# SC8701_EVM_RE1_0624.net
KiCad netlist of a schematic drawn in Altium Designer
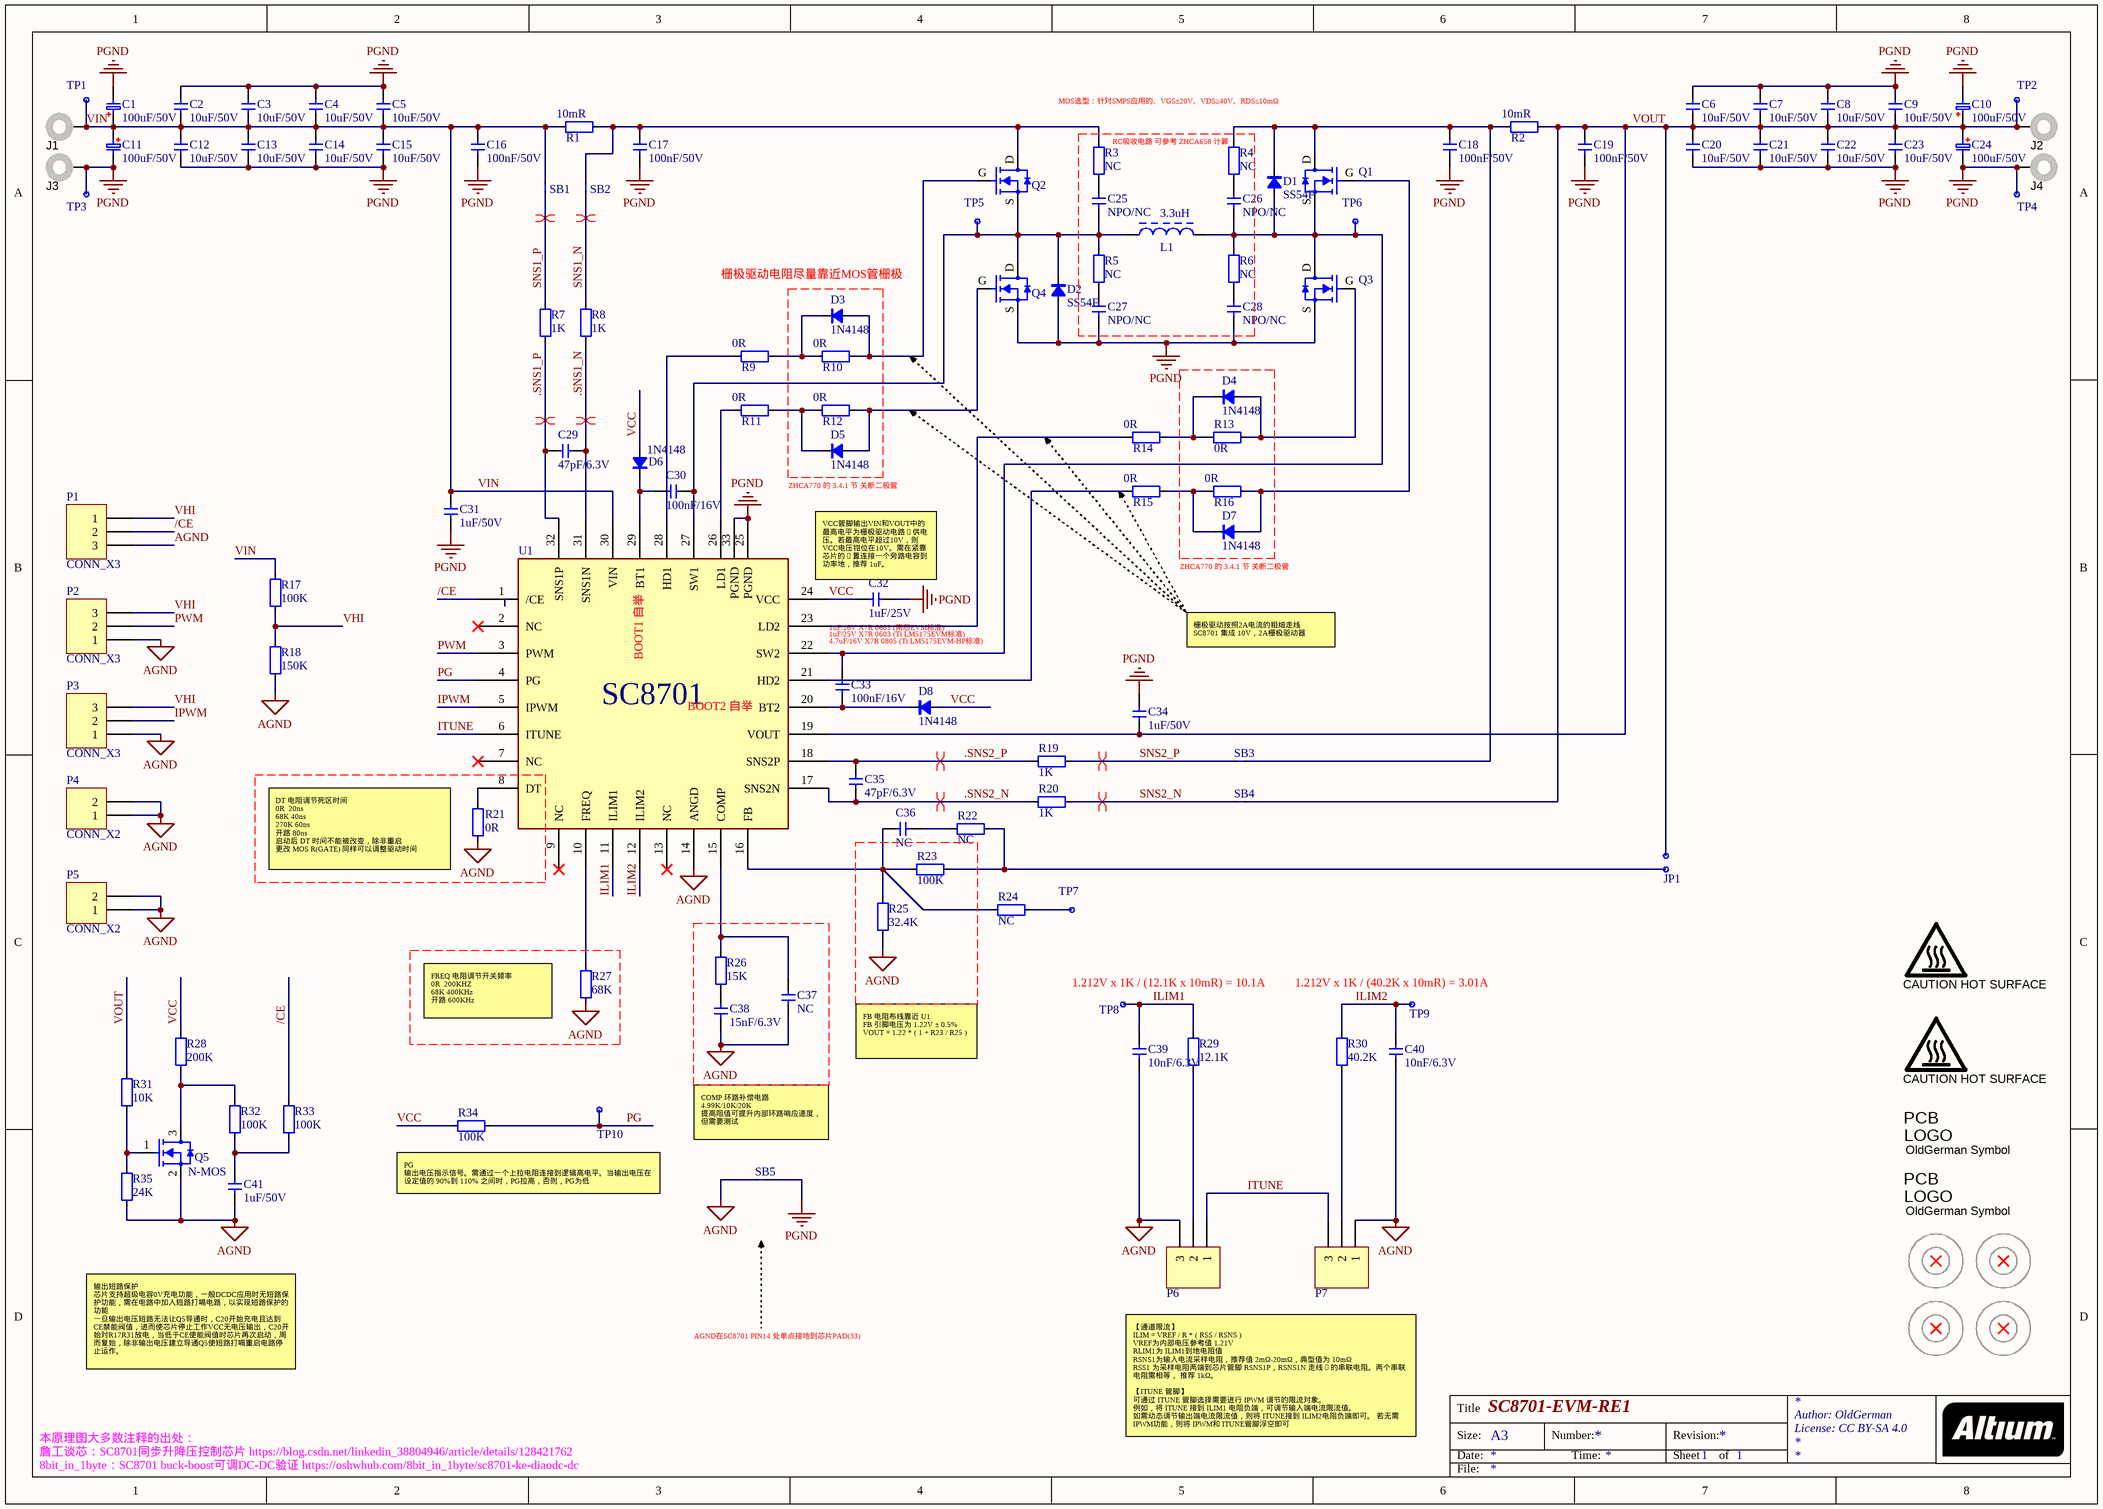
[diagram p0: SC8701_EVM_RE1_0624.SchDoc]

(export (version "E")
  (design (tool "Eeschema 10.0.6"))
  (components
    (comp (ref "C1")
      (value "100uF/50V")
      (footprint "CAP OS-CON D=10.0 L=10.0 F10")
      (description "Capacitor")
      (libsource (lib "ODG_AD_Lib") (part "CAP_Polar_Aluminum"))
    )
    (comp (ref "C2")
      (value "10uF/50V")
      (footprint "C1210")
      (description "Capacitor")
      (libsource (lib "ODG_AD_Lib") (part "CAP"))
    )
    (comp (ref "C3")
      (value "10uF/50V")
      (footprint "C1210")
      (description "Capacitor")
      (libsource (lib "ODG_AD_Lib") (part "CAP"))
    )
    (comp (ref "C4")
      (value "10uF/50V")
      (footprint "C1210")
      (description "Capacitor")
      (libsource (lib "ODG_AD_Lib") (part "CAP"))
    )
    (comp (ref "C5")
      (value "10uF/50V")
      (footprint "C1210")
      (description "Capacitor")
      (libsource (lib "ODG_AD_Lib") (part "CAP"))
    )
    (comp (ref "C6")
      (value "10uF/50V")
      (footprint "C1210")
      (description "Capacitor")
      (libsource (lib "ODG_AD_Lib") (part "CAP"))
    )
    (comp (ref "C7")
      (value "10uF/50V")
      (footprint "C1210")
      (description "Capacitor")
      (libsource (lib "ODG_AD_Lib") (part "CAP"))
    )
    (comp (ref "C8")
      (value "10uF/50V")
      (footprint "C1210")
      (description "Capacitor")
      (libsource (lib "ODG_AD_Lib") (part "CAP"))
    )
    (comp (ref "C9")
      (value "10uF/50V")
      (footprint "C1210")
      (description "Capacitor")
      (libsource (lib "ODG_AD_Lib") (part "CAP"))
    )
    (comp (ref "C10")
      (value "100uF/50V")
      (footprint "CAP OS-CON D=10.0 L=10.0 F10")
      (description "Capacitor")
      (libsource (lib "ODG_AD_Lib") (part "CAP_Polar_Aluminum"))
    )
    (comp (ref "C11")
      (value "100uF/50V")
      (footprint "CAP OS-CON D=10.0 L=10.0 F10")
      (description "Capacitor")
      (libsource (lib "ODG_AD_Lib") (part "CAP_Polar_Aluminum"))
    )
    (comp (ref "C12")
      (value "10uF/50V")
      (footprint "C1210")
      (description "Capacitor")
      (libsource (lib "ODG_AD_Lib") (part "CAP"))
    )
    (comp (ref "C13")
      (value "10uF/50V")
      (footprint "C1210")
      (description "Capacitor")
      (libsource (lib "ODG_AD_Lib") (part "CAP"))
    )
    (comp (ref "C14")
      (value "10uF/50V")
      (footprint "C1210")
      (description "Capacitor")
      (libsource (lib "ODG_AD_Lib") (part "CAP"))
    )
    (comp (ref "C15")
      (value "10uF/50V")
      (footprint "C1210")
      (description "Capacitor")
      (libsource (lib "ODG_AD_Lib") (part "CAP"))
    )
    (comp (ref "C16")
      (value "100nF/50V")
      (footprint "C0603")
      (description "Capacitor")
      (libsource (lib "ODG_AD_Lib") (part "CAP"))
    )
    (comp (ref "C17")
      (value "100nF/50V")
      (footprint "C0603")
      (description "Capacitor")
      (libsource (lib "ODG_AD_Lib") (part "CAP"))
    )
    (comp (ref "C18")
      (value "100nF/50V")
      (footprint "C0603")
      (description "Capacitor")
      (libsource (lib "ODG_AD_Lib") (part "CAP"))
    )
    (comp (ref "C19")
      (value "100nF/50V")
      (footprint "C0603")
      (description "Capacitor")
      (libsource (lib "ODG_AD_Lib") (part "CAP"))
    )
    (comp (ref "C20")
      (value "10uF/50V")
      (footprint "C1210")
      (description "Capacitor")
      (libsource (lib "ODG_AD_Lib") (part "CAP"))
    )
    (comp (ref "C21")
      (value "10uF/50V")
      (footprint "C1210")
      (description "Capacitor")
      (libsource (lib "ODG_AD_Lib") (part "CAP"))
    )
    (comp (ref "C22")
      (value "10uF/50V")
      (footprint "C1210")
      (description "Capacitor")
      (libsource (lib "ODG_AD_Lib") (part "CAP"))
    )
    (comp (ref "C23")
      (value "10uF/50V")
      (footprint "C1210")
      (description "Capacitor")
      (libsource (lib "ODG_AD_Lib") (part "CAP"))
    )
    (comp (ref "C24")
      (value "100uF/50V")
      (footprint "CAP OS-CON D=10.0 L=10.0 F10")
      (description "Capacitor")
      (libsource (lib "ODG_AD_Lib") (part "CAP_Polar_Aluminum"))
    )
    (comp (ref "C25")
      (value "NPO/NC")
      (footprint "C0805")
      (description "Capacitor")
      (libsource (lib "ODG_AD_Lib") (part "CAP"))
    )
    (comp (ref "C26")
      (value "NPO/NC")
      (footprint "C0805")
      (description "Capacitor")
      (libsource (lib "ODG_AD_Lib") (part "CAP"))
    )
    (comp (ref "C27")
      (value "NPO/NC")
      (footprint "C0805")
      (description "Capacitor")
      (libsource (lib "ODG_AD_Lib") (part "CAP"))
    )
    (comp (ref "C28")
      (value "NPO/NC")
      (footprint "C0805")
      (description "Capacitor")
      (libsource (lib "ODG_AD_Lib") (part "CAP"))
    )
    (comp (ref "C29")
      (value "47pF/6.3V")
      (footprint "C0603")
      (description "Capacitor")
      (libsource (lib "ODG_AD_Lib") (part "CAP"))
    )
    (comp (ref "C30")
      (value "100nF/16V")
      (footprint "C0603")
      (description "Capacitor")
      (libsource (lib "ODG_AD_Lib") (part "CAP"))
    )
    (comp (ref "C31")
      (value "1uF/50V")
      (footprint "C0603")
      (description "Capacitor")
      (libsource (lib "ODG_AD_Lib") (part "CAP"))
    )
    (comp (ref "C32")
      (value "1uF/25V")
      (footprint "C0805")
      (description "Capacitor")
      (libsource (lib "ODG_AD_Lib") (part "CAP"))
    )
    (comp (ref "C33")
      (value "100nF/16V")
      (footprint "C0603")
      (description "Capacitor")
      (libsource (lib "ODG_AD_Lib") (part "CAP"))
    )
    (comp (ref "C34")
      (value "1uF/50V")
      (footprint "C0603")
      (description "Capacitor")
      (libsource (lib "ODG_AD_Lib") (part "CAP"))
    )
    (comp (ref "C35")
      (value "47pF/6.3V")
      (footprint "C0603")
      (description "Capacitor")
      (libsource (lib "ODG_AD_Lib") (part "CAP"))
    )
    (comp (ref "C36")
      (value "NC")
      (footprint "C0603")
      (description "Capacitor")
      (libsource (lib "ODG_AD_Lib") (part "CAP"))
    )
    (comp (ref "C37")
      (value "NC")
      (footprint "C0603")
      (description "Capacitor")
      (libsource (lib "ODG_AD_Lib") (part "CAP"))
    )
    (comp (ref "C38")
      (value "15nF/6.3V")
      (footprint "C0603")
      (description "Capacitor")
      (libsource (lib "ODG_AD_Lib") (part "CAP"))
    )
    (comp (ref "C39")
      (value "10nF/6.3V")
      (footprint "C0603")
      (description "Capacitor")
      (libsource (lib "ODG_AD_Lib") (part "CAP"))
    )
    (comp (ref "C40")
      (value "10nF/6.3V")
      (footprint "C0603")
      (description "Capacitor")
      (libsource (lib "ODG_AD_Lib") (part "CAP"))
    )
    (comp (ref "C41")
      (value "1uF/50V")
      (footprint "C0603")
      (description "Capacitor")
      (libsource (lib "ODG_AD_Lib") (part "CAP"))
    )
    (comp (ref "D1")
      (value "SS54F")
      (footprint "SMAF")
      (description "二极管")
      (libsource (lib "") (part "DIODE_2"))
    )
    (comp (ref "D2")
      (value "SS54F")
      (footprint "SMAF")
      (description "二极管")
      (libsource (lib "") (part "DIODE_2"))
    )
    (comp (ref "D3")
      (value "1N4148")
      (footprint "SOD-323")
      (description "二极管")
      (libsource (lib "ODG_AD_Lib") (part "DIODE"))
    )
    (comp (ref "D4")
      (value "1N4148")
      (footprint "SOD-323")
      (description "二极管")
      (libsource (lib "ODG_AD_Lib") (part "DIODE"))
    )
    (comp (ref "D5")
      (value "1N4148")
      (footprint "SOD-323")
      (description "二极管")
      (libsource (lib "ODG_AD_Lib") (part "DIODE"))
    )
    (comp (ref "D6")
      (value "1N4148")
      (footprint "SOD-323")
      (description "二极管")
      (libsource (lib "") (part "DIODE_1"))
    )
    (comp (ref "D7")
      (value "1N4148")
      (footprint "SOD-323")
      (description "二极管")
      (libsource (lib "ODG_AD_Lib") (part "DIODE"))
    )
    (comp (ref "D8")
      (value "1N4148")
      (footprint "SOD-323")
      (description "二极管")
      (libsource (lib "ODG_AD_Lib") (part "DIODE"))
    )
    (comp (ref "H1") (value "HOLE") (footprint "M3.2 D=8") (libsource (lib "ODG_AD_Lib") (part "HOLE")))
    (comp (ref "H2") (value "HOLE") (footprint "M3.2 D=8") (libsource (lib "ODG_AD_Lib") (part "HOLE")))
    (comp (ref "H3") (value "HOLE") (footprint "M3.2 D=8") (libsource (lib "ODG_AD_Lib") (part "HOLE")))
    (comp (ref "H4") (value "HOLE") (footprint "M3.2 D=8") (libsource (lib "ODG_AD_Lib") (part "HOLE")))
    (comp (ref "J1")
      (value "U6047")
      (footprint "JACK_BANANA_U6047")
      (description "Banana Jack")
      (fields
        (field (name "PARTNUMBER") "575-8")
        (field (name "MANUFACTURER") "Keystone")
        (field (name "PUBLISHER") "Texas Instruments")
      )
      (libsource (lib "ODG_AD_Lib") (part "JACK_BANANA"))
    )
    (comp (ref "J2")
      (value "U6047")
      (footprint "JACK_BANANA_U6047")
      (description "Banana Jack")
      (fields
        (field (name "PARTNUMBER") "575-8")
        (field (name "MANUFACTURER") "Keystone")
        (field (name "PUBLISHER") "Texas Instruments")
      )
      (libsource (lib "ODG_AD_Lib") (part "JACK_BANANA"))
    )
    (comp (ref "J3")
      (value "U6047")
      (footprint "JACK_BANANA_U6047")
      (description "Banana Jack")
      (fields
        (field (name "PARTNUMBER") "575-8")
        (field (name "MANUFACTURER") "Keystone")
        (field (name "PUBLISHER") "Texas Instruments")
      )
      (libsource (lib "ODG_AD_Lib") (part "JACK_BANANA"))
    )
    (comp (ref "J4")
      (value "U6047")
      (footprint "JACK_BANANA_U6047")
      (description "Banana Jack")
      (fields
        (field (name "PARTNUMBER") "575-8")
        (field (name "MANUFACTURER") "Keystone")
        (field (name "PUBLISHER") "Texas Instruments")
      )
      (libsource (lib "ODG_AD_Lib") (part "JACK_BANANA"))
    )
    (comp (ref "JP1")
      (value "CONN_X2_DOT")
      (footprint "2.54mm_Male_x2")
      (libsource (lib "ODG_AD_Lib") (part "CONN_X2_DOT"))
    )
    (comp (ref "L1")
      (value "3.3uH")
      (footprint "INDUCTOR 1350 12.6X13.5X5.0mm")
      (description "135 功率电感 额定电流15A")
      (libsource (lib "ODG_AD_Lib") (part "Inductor_power"))
    )
    (comp (ref "LOGO1")
      (value "CAUTION HOT SURFACE")
      (footprint "IEC_HotSurface_Small")
      (description "IEC 61010-1 Hot Surface Warning")
      (fields (field (name "SYMBOLCREATOR") "a0412235") (field (name "PUBLISHER") "Texas Instruments"))
      (libsource (lib "ODG_AD_Lib") (part "IEC_HotSurface"))
    )
    (comp (ref "LOGO2")
      (value "CAUTION HOT SURFACE")
      (footprint "IEC_HotSurface_Small")
      (description "IEC 61010-1 Hot Surface Warning")
      (fields (field (name "SYMBOLCREATOR") "a0412235") (field (name "PUBLISHER") "Texas Instruments"))
      (libsource (lib "ODG_AD_Lib") (part "IEC_HotSurface"))
    )
    (comp (ref "Logo3")
      (value "OldGerman Symbol")
      (footprint "ODG_LOGO")
      (fields (field (name "SYMBOLCREATOR") "a0412235") (field (name "PUBLISHER") "Texas Instruments"))
      (libsource (lib "ODG_AD_Lib") (part "OldGeman"))
    )
    (comp (ref "Logo4")
      (value "OldGerman Symbol")
      (footprint "ODG_LOGO")
      (fields (field (name "SYMBOLCREATOR") "a0412235") (field (name "PUBLISHER") "Texas Instruments"))
      (libsource (lib "ODG_AD_Lib") (part "OldGeman"))
    )
    (comp (ref "P1") (value "CONN_X3") (footprint "2.54mm_Male_x3") (libsource (lib "") (part "CONN_X3_1")))
    (comp (ref "P2")
      (value "CONN_X3")
      (footprint "2.54mm_Male_x3")
      (libsource (lib "ODG_AD_Lib") (part "CONN_X3"))
    )
    (comp (ref "P3")
      (value "CONN_X3")
      (footprint "2.54mm_Male_x3")
      (libsource (lib "ODG_AD_Lib") (part "CONN_X3"))
    )
    (comp (ref "P4")
      (value "CONN_X2")
      (footprint "2.54mm_Male_x2")
      (libsource (lib "ODG_AD_Lib") (part "CONN_X2"))
    )
    (comp (ref "P5")
      (value "CONN_X2")
      (footprint "2.54mm_Male_x2")
      (libsource (lib "ODG_AD_Lib") (part "CONN_X2"))
    )
    (comp (ref "P6") (value "CONN_X3") (footprint "2.54mm_Male_x3") (libsource (lib "") (part "CONN_X3_1")))
    (comp (ref "P7") (value "CONN_X3") (footprint "2.54mm_Male_x3") (libsource (lib "") (part "CONN_X3_1")))
    (comp (ref "Q1")
      (value "N-MOS_GDS")
      (footprint "SO8FL ROUND")
      (libsource (lib "ODG_AD_Lib") (part "N-MOS_GDS"))
    )
    (comp (ref "Q2")
      (value "N-MOS_GDS")
      (footprint "SO8FL ROUND")
      (libsource (lib "ODG_AD_Lib") (part "N-MOS_GDS"))
    )
    (comp (ref "Q3")
      (value "N-MOS_GDS")
      (footprint "SO8FL ROUND")
      (libsource (lib "ODG_AD_Lib") (part "N-MOS_GDS"))
    )
    (comp (ref "Q4")
      (value "N-MOS_GDS")
      (footprint "SO8FL ROUND")
      (libsource (lib "ODG_AD_Lib") (part "N-MOS_GDS"))
    )
    (comp (ref "Q5")
      (value "N-MOS")
      (footprint "INFINEON SOT-23-3")
      (libsource (lib "ODG_AD_Lib") (part "N-MOS_123"))
    )
    (comp (ref "R1")
      (value "10mR")
      (footprint "R1206")
      (description "IEC Standard")
      (libsource (lib "ODG_AD_Lib") (part "RES"))
    )
    (comp (ref "R2")
      (value "10mR")
      (footprint "R1206")
      (description "IEC Standard")
      (libsource (lib "ODG_AD_Lib") (part "RES"))
    )
    (comp (ref "R3")
      (value "NC")
      (footprint "R0805")
      (description "IEC Standard")
      (libsource (lib "") (part "RES_1"))
    )
    (comp (ref "R4")
      (value "NC")
      (footprint "R0805")
      (description "IEC Standard")
      (libsource (lib "") (part "RES_1"))
    )
    (comp (ref "R5")
      (value "NC")
      (footprint "R0805")
      (description "IEC Standard")
      (libsource (lib "") (part "RES_1"))
    )
    (comp (ref "R6")
      (value "NC")
      (footprint "R0805")
      (description "IEC Standard")
      (libsource (lib "") (part "RES_1"))
    )
    (comp (ref "R7")
      (value "1K")
      (footprint "R0603")
      (description "IEC Standard")
      (libsource (lib "") (part "RES_1"))
    )
    (comp (ref "R8")
      (value "1K")
      (footprint "R0603")
      (description "IEC Standard")
      (libsource (lib "") (part "RES_1"))
    )
    (comp (ref "R9")
      (value "0R")
      (footprint "R0603")
      (description "IEC Standard")
      (libsource (lib "ODG_AD_Lib") (part "RES"))
    )
    (comp (ref "R10")
      (value "0R")
      (footprint "R0603")
      (description "IEC Standard")
      (libsource (lib "ODG_AD_Lib") (part "RES"))
    )
    (comp (ref "R11")
      (value "0R")
      (footprint "R0603")
      (description "IEC Standard")
      (libsource (lib "ODG_AD_Lib") (part "RES"))
    )
    (comp (ref "R12")
      (value "0R")
      (footprint "R0603")
      (description "IEC Standard")
      (libsource (lib "ODG_AD_Lib") (part "RES"))
    )
    (comp (ref "R13")
      (value "0R")
      (footprint "R0603")
      (description "IEC Standard")
      (libsource (lib "ODG_AD_Lib") (part "RES"))
    )
    (comp (ref "R14")
      (value "0R")
      (footprint "R0603")
      (description "IEC Standard")
      (libsource (lib "ODG_AD_Lib") (part "RES"))
    )
    (comp (ref "R15")
      (value "0R")
      (footprint "R0603")
      (description "IEC Standard")
      (libsource (lib "ODG_AD_Lib") (part "RES"))
    )
    (comp (ref "R16")
      (value "0R")
      (footprint "R0603")
      (description "IEC Standard")
      (libsource (lib "ODG_AD_Lib") (part "RES"))
    )
    (comp (ref "R17")
      (value "100K")
      (footprint "R0603")
      (description "IEC Standard")
      (libsource (lib "") (part "RES_1"))
    )
    (comp (ref "R18")
      (value "150K")
      (footprint "R0603")
      (description "IEC Standard")
      (libsource (lib "") (part "RES_1"))
    )
    (comp (ref "R19")
      (value "1K")
      (footprint "R0603")
      (description "IEC Standard")
      (libsource (lib "") (part "RES_2"))
    )
    (comp (ref "R20")
      (value "1K")
      (footprint "R0603")
      (description "IEC Standard")
      (libsource (lib "") (part "RES_2"))
    )
    (comp (ref "R21")
      (value "0R")
      (footprint "R0603")
      (description "IEC Standard")
      (libsource (lib "") (part "RES_1"))
    )
    (comp (ref "R22")
      (value "NC")
      (footprint "R0603")
      (description "IEC Standard")
      (libsource (lib "") (part "RES_2"))
    )
    (comp (ref "R23")
      (value "100K")
      (footprint "R0603")
      (description "IEC Standard")
      (libsource (lib "ODG_AD_Lib") (part "RES"))
    )
    (comp (ref "R24")
      (value "NC")
      (footprint "R0603")
      (description "IEC Standard")
      (libsource (lib "") (part "RES_2"))
    )
    (comp (ref "R25")
      (value "32.4K")
      (footprint "R0603")
      (description "IEC Standard")
      (libsource (lib "") (part "RES_1"))
    )
    (comp (ref "R26")
      (value "15K")
      (footprint "R0603")
      (description "IEC Standard")
      (libsource (lib "") (part "RES_1"))
    )
    (comp (ref "R27")
      (value "68K")
      (footprint "R0603")
      (description "IEC Standard")
      (libsource (lib "") (part "RES_1"))
    )
    (comp (ref "R28")
      (value "200K")
      (footprint "R0603")
      (description "IEC Standard")
      (libsource (lib "") (part "RES_1"))
    )
    (comp (ref "R29")
      (value "12.1K")
      (footprint "R0603")
      (description "IEC Standard")
      (libsource (lib "") (part "RES_1"))
    )
    (comp (ref "R30")
      (value "40.2K")
      (footprint "R0603")
      (description "IEC Standard")
      (libsource (lib "") (part "RES_1"))
    )
    (comp (ref "R31")
      (value "10K")
      (footprint "R0603")
      (description "IEC Standard")
      (libsource (lib "") (part "RES_1"))
    )
    (comp (ref "R32")
      (value "100K")
      (footprint "R0603")
      (description "IEC Standard")
      (libsource (lib "") (part "RES_1"))
    )
    (comp (ref "R33")
      (value "100K")
      (footprint "R0603")
      (description "IEC Standard")
      (libsource (lib "") (part "RES_1"))
    )
    (comp (ref "R34")
      (value "100K")
      (footprint "R0603")
      (description "IEC Standard")
      (libsource (lib "ODG_AD_Lib") (part "RES"))
    )
    (comp (ref "R35")
      (value "24K")
      (footprint "R0603")
      (description "IEC Standard")
      (libsource (lib "") (part "RES_1"))
    )
    (comp (ref "SB1")
      (value "NetTie_200um")
      (footprint "NetTie_200um")
      (description "Net Tie")
      (fields (field (name "PART NUMBER") "NetTie 0.2mm") (field (name "PUBLISHER") "Nordic Semiconductor"))
      (libsource (lib "pca63100") (part "NetTie 0.2mm"))
    )
    (comp (ref "SB2")
      (value "NetTie_200um")
      (footprint "NetTie_200um")
      (description "Net Tie")
      (fields (field (name "PART NUMBER") "NetTie 0.2mm") (field (name "PUBLISHER") "Nordic Semiconductor"))
      (libsource (lib "pca63100") (part "NetTie 0.2mm"))
    )
    (comp (ref "SB3")
      (value "NetTie_200um")
      (footprint "NetTie_200um")
      (description "Net Tie")
      (fields (field (name "PART NUMBER") "NetTie 0.2mm") (field (name "PUBLISHER") "Nordic Semiconductor"))
      (libsource (lib "pca63100") (part "NetTie 0.2mm"))
    )
    (comp (ref "SB4")
      (value "NetTie_200um")
      (footprint "NetTie_200um")
      (description "Net Tie")
      (fields (field (name "PART NUMBER") "NetTie 0.2mm") (field (name "PUBLISHER") "Nordic Semiconductor"))
      (libsource (lib "pca63100") (part "NetTie 0.2mm"))
    )
    (comp (ref "SB5")
      (value "NetTie_200um")
      (footprint "NetTie_200um")
      (description "Net Tie")
      (fields (field (name "PART NUMBER") "NetTie 0.2mm") (field (name "PUBLISHER") "Nordic Semiconductor"))
      (libsource (lib "pca63100") (part "NetTie 0.2mm"))
    )
    (comp (ref "TP1")
      (value "CONN_X1_DOT")
      (footprint "2.54mm_Male_x1")
      (libsource (lib "ODG_AD_Lib") (part "CONN_X1_DOT"))
    )
    (comp (ref "TP2")
      (value "CONN_X1_DOT")
      (footprint "2.54mm_Male_x1")
      (libsource (lib "ODG_AD_Lib") (part "CONN_X1_DOT"))
    )
    (comp (ref "TP3")
      (value "CONN_X1_DOT")
      (footprint "2.54mm_Male_x1")
      (libsource (lib "ODG_AD_Lib") (part "CONN_X1_DOT"))
    )
    (comp (ref "TP4")
      (value "CONN_X1_DOT")
      (footprint "2.54mm_Male_x1")
      (libsource (lib "ODG_AD_Lib") (part "CONN_X1_DOT"))
    )
    (comp (ref "TP5")
      (value "CONN_X1_DOT")
      (footprint "2.54mm_Male_x1")
      (libsource (lib "ODG_AD_Lib") (part "CONN_X1_DOT"))
    )
    (comp (ref "TP6")
      (value "CONN_X1_DOT")
      (footprint "2.54mm_Male_x1")
      (libsource (lib "ODG_AD_Lib") (part "CONN_X1_DOT"))
    )
    (comp (ref "TP7")
      (value "CONN_X1_DOT")
      (footprint "2.54mm_Male_x1")
      (libsource (lib "ODG_AD_Lib") (part "CONN_X1_DOT"))
    )
    (comp (ref "TP8")
      (value "CONN_X1_DOT")
      (footprint "2.54mm_Male_x1")
      (libsource (lib "ODG_AD_Lib") (part "CONN_X1_DOT"))
    )
    (comp (ref "TP9")
      (value "CONN_X1_DOT")
      (footprint "2.54mm_Male_x1")
      (libsource (lib "ODG_AD_Lib") (part "CONN_X1_DOT"))
    )
    (comp (ref "TP10")
      (value "CONN_X1_DOT")
      (footprint "2.54mm_Male_x1")
      (libsource (lib "ODG_AD_Lib") (part "CONN_X1_DOT"))
    )
    (comp (ref "U1")
      (value "SC8701 (A)")
      (footprint "TQFN-32 4X4MM 0.4 VIA")
      (description "高效率, 同步, 4 管升降压控制器")
      (libsource (lib "ODG_AD_Lib") (part "SC8701 (A)"))
    )
  )
  (nets
    (net (code "1") (name "/.SNS1_N") (class "Default")
      (node (ref "C29") (pin "2") (pinfunction "2_2") (pintype "passive"))
      (node (ref "R8") (pin "1") (pinfunction "1_1") (pintype "passive"))
      (node (ref "U1") (pin "31") (pinfunction "SNS1N_31") (pintype "passive"))
    )
    (net (code "2") (name "/.SNS1_P") (class "Default")
      (node (ref "C29") (pin "1") (pinfunction "1_1") (pintype "passive"))
      (node (ref "R7") (pin "1") (pinfunction "1_1") (pintype "passive"))
      (node (ref "U1") (pin "32") (pinfunction "SNS1P_32") (pintype "passive"))
    )
    (net (code "3") (name "/.SNS2_N") (class "Default")
      (node (ref "C35") (pin "2") (pinfunction "2_2") (pintype "passive"))
      (node (ref "R20") (pin "2") (pinfunction "2_2") (pintype "passive"))
      (node (ref "U1") (pin "17") (pinfunction "SNS2N_17") (pintype "passive"))
    )
    (net (code "4") (name "/.SNS2_P") (class "Default")
      (node (ref "C35") (pin "1") (pinfunction "1_1") (pintype "passive"))
      (node (ref "R19") (pin "2") (pinfunction "2_2") (pintype "passive"))
      (node (ref "U1") (pin "18") (pinfunction "SNS2P_18") (pintype "passive"))
    )
    (net (code "5") (name "/ILIM1") (class "Default")
      (node (ref "C39") (pin "2") (pinfunction "2_2") (pintype "passive"))
      (node (ref "R29") (pin "2") (pinfunction "2_2") (pintype "passive"))
      (node (ref "TP8") (pin "1") (pinfunction "1_1") (pintype "passive"))
      (node (ref "U1") (pin "11") (pinfunction "ILIM1_11") (pintype "passive"))
    )
    (net (code "6") (name "/ILIM2") (class "Default")
      (node (ref "C40") (pin "2") (pinfunction "2_2") (pintype "passive"))
      (node (ref "R30") (pin "2") (pinfunction "2_2") (pintype "passive"))
      (node (ref "TP9") (pin "1") (pinfunction "1_1") (pintype "passive"))
      (node (ref "U1") (pin "12") (pinfunction "ILIM2_12") (pintype "passive"))
    )
    (net (code "7") (name "/IPWM") (class "Default")
      (node (ref "P3") (pin "2") (pinfunction "2_2") (pintype "passive"))
      (node (ref "U1") (pin "5") (pinfunction "IPWM_5") (pintype "passive"))
    )
    (net (code "8") (name "/ITUNE") (class "Default")
      (node (ref "P6") (pin "1") (pinfunction "1_1") (pintype "passive"))
      (node (ref "P7") (pin "3") (pinfunction "3_3") (pintype "passive"))
      (node (ref "U1") (pin "6") (pinfunction "ITUNE_6") (pintype "passive"))
    )
    (net (code "9") (name "/PG") (class "Default")
      (node (ref "R34") (pin "2") (pinfunction "2_2") (pintype "passive"))
      (node (ref "TP10") (pin "1") (pinfunction "1_1") (pintype "passive"))
      (node (ref "U1") (pin "4") (pinfunction "PG_4") (pintype "passive"))
    )
    (net (code "10") (name "/PWM") (class "Default")
      (node (ref "P2") (pin "2") (pinfunction "2_2") (pintype "passive"))
      (node (ref "U1") (pin "3") (pinfunction "PWM_3") (pintype "passive"))
    )
    (net (code "11") (name "/SNS1_N") (class "Default")
      (node (ref "R8") (pin "2") (pinfunction "2_2") (pintype "passive"))
      (node (ref "SB2") (pin "1") (pinfunction "1_1") (pintype "passive"))
    )
    (net (code "12") (name "/SNS1_P") (class "Default")
      (node (ref "R7") (pin "2") (pinfunction "2_2") (pintype "passive"))
      (node (ref "SB1") (pin "1") (pinfunction "1_1") (pintype "passive"))
    )
    (net (code "13") (name "/SNS2_N") (class "Default")
      (node (ref "R20") (pin "1") (pinfunction "1_1") (pintype "passive"))
      (node (ref "SB4") (pin "1") (pinfunction "1_1") (pintype "passive"))
    )
    (net (code "14") (name "/SNS2_P") (class "Default")
      (node (ref "R19") (pin "1") (pinfunction "1_1") (pintype "passive"))
      (node (ref "SB3") (pin "1") (pinfunction "1_1") (pintype "passive"))
    )
    (net (code "15") (name "/VCC") (class "Default")
      (node (ref "C32") (pin "1") (pinfunction "1_1") (pintype "passive"))
      (node (ref "D6") (pin "1") (pinfunction "A_1") (pintype "passive"))
      (node (ref "D8") (pin "1") (pinfunction "A_1") (pintype "passive"))
      (node (ref "R28") (pin "2") (pinfunction "2_2") (pintype "passive"))
      (node (ref "R34") (pin "1") (pinfunction "1_1") (pintype "passive"))
      (node (ref "U1") (pin "24") (pinfunction "VCC_24") (pintype "passive"))
    )
    (net (code "16") (name "/VHI") (class "Default")
      (node (ref "P1") (pin "1") (pinfunction "1_1") (pintype "passive"))
      (node (ref "P2") (pin "3") (pinfunction "3_3") (pintype "passive"))
      (node (ref "P3") (pin "3") (pinfunction "3_3") (pintype "passive"))
      (node (ref "R17") (pin "1") (pinfunction "1_1") (pintype "passive"))
      (node (ref "R18") (pin "2") (pinfunction "2_2") (pintype "passive"))
    )
    (net (code "17") (name "/VIN") (class "Default")
      (node (ref "C1") (pin "1") (pinfunction "1_1") (pintype "passive"))
      (node (ref "C11") (pin "1") (pinfunction "1_1") (pintype "passive"))
      (node (ref "C12") (pin "2") (pinfunction "2_2") (pintype "passive"))
      (node (ref "C13") (pin "2") (pinfunction "2_2") (pintype "passive"))
      (node (ref "C14") (pin "2") (pinfunction "2_2") (pintype "passive"))
      (node (ref "C15") (pin "2") (pinfunction "2_2") (pintype "passive"))
      (node (ref "C16") (pin "2") (pinfunction "2_2") (pintype "passive"))
      (node (ref "C2") (pin "2") (pinfunction "2_2") (pintype "passive"))
      (node (ref "C3") (pin "2") (pinfunction "2_2") (pintype "passive"))
      (node (ref "C31") (pin "1") (pinfunction "1_1") (pintype "passive"))
      (node (ref "C4") (pin "2") (pinfunction "2_2") (pintype "passive"))
      (node (ref "C5") (pin "2") (pinfunction "2_2") (pintype "passive"))
      (node (ref "J1") (pin "1") (pinfunction "1_1") (pintype "passive"))
      (node (ref "R1") (pin "1") (pinfunction "1_1") (pintype "passive"))
      (node (ref "R17") (pin "2") (pinfunction "2_2") (pintype "passive"))
      (node (ref "SB1") (pin "2") (pinfunction "2_2") (pintype "passive"))
      (node (ref "TP1") (pin "1") (pinfunction "1_1") (pintype "passive"))
      (node (ref "U1") (pin "30") (pinfunction "VIN_30") (pintype "passive"))
    )
    (net (code "18") (name "/VOUT") (class "Default")
      (node (ref "C10") (pin "1") (pinfunction "1_1") (pintype "passive"))
      (node (ref "C19") (pin "2") (pinfunction "2_2") (pintype "passive"))
      (node (ref "C20") (pin "2") (pinfunction "2_2") (pintype "passive"))
      (node (ref "C21") (pin "2") (pinfunction "2_2") (pintype "passive"))
      (node (ref "C22") (pin "2") (pinfunction "2_2") (pintype "passive"))
      (node (ref "C23") (pin "2") (pinfunction "2_2") (pintype "passive"))
      (node (ref "C24") (pin "1") (pinfunction "1_1") (pintype "passive"))
      (node (ref "C34") (pin "1") (pinfunction "1_1") (pintype "passive"))
      (node (ref "C6") (pin "2") (pinfunction "2_2") (pintype "passive"))
      (node (ref "C7") (pin "2") (pinfunction "2_2") (pintype "passive"))
      (node (ref "C8") (pin "2") (pinfunction "2_2") (pintype "passive"))
      (node (ref "C9") (pin "2") (pinfunction "2_2") (pintype "passive"))
      (node (ref "J2") (pin "1") (pinfunction "1_1") (pintype "passive"))
      (node (ref "JP1") (pin "1") (pinfunction "1_1") (pintype "passive"))
      (node (ref "R2") (pin "2") (pinfunction "2_2") (pintype "passive"))
      (node (ref "R31") (pin "2") (pinfunction "2_2") (pintype "passive"))
      (node (ref "SB4") (pin "2") (pinfunction "2_2") (pintype "passive"))
      (node (ref "TP2") (pin "1") (pinfunction "1_1") (pintype "passive"))
      (node (ref "U1") (pin "19") (pinfunction "VOUT_19") (pintype "passive"))
    )
    (net (code "19") (name "/{slash}CE") (class "Default")
      (node (ref "P1") (pin "2") (pinfunction "2_2") (pintype "passive"))
      (node (ref "R33") (pin "2") (pinfunction "2_2") (pintype "passive"))
      (node (ref "U1") (pin "1") (pinfunction "/CE_1") (pintype "passive"))
    )
    (net (code "20") (name "AGND") (class "Default")
      (node (ref "C37") (pin "1") (pinfunction "1_1") (pintype "passive"))
      (node (ref "C38") (pin "1") (pinfunction "1_1") (pintype "passive"))
      (node (ref "C39") (pin "1") (pinfunction "1_1") (pintype "passive"))
      (node (ref "C40") (pin "1") (pinfunction "1_1") (pintype "passive"))
      (node (ref "C41") (pin "2") (pinfunction "2_2") (pintype "passive"))
      (node (ref "P1") (pin "3") (pinfunction "3_3") (pintype "passive"))
      (node (ref "P2") (pin "1") (pinfunction "1_1") (pintype "passive"))
      (node (ref "P3") (pin "1") (pinfunction "1_1") (pintype "passive"))
      (node (ref "P4") (pin "1") (pinfunction "1_1") (pintype "passive"))
      (node (ref "P4") (pin "2") (pinfunction "2_2") (pintype "passive"))
      (node (ref "P5") (pin "1") (pinfunction "1_1") (pintype "passive"))
      (node (ref "P5") (pin "2") (pinfunction "2_2") (pintype "passive"))
      (node (ref "P6") (pin "3") (pinfunction "3_3") (pintype "passive"))
      (node (ref "P7") (pin "1") (pinfunction "1_1") (pintype "passive"))
      (node (ref "Q5") (pin "2") (pinfunction "S_2") (pintype "passive"))
      (node (ref "R18") (pin "1") (pinfunction "1_1") (pintype "passive"))
      (node (ref "R21") (pin "1") (pinfunction "1_1") (pintype "passive"))
      (node (ref "R25") (pin "1") (pinfunction "1_1") (pintype "passive"))
      (node (ref "R27") (pin "1") (pinfunction "1_1") (pintype "passive"))
      (node (ref "R35") (pin "1") (pinfunction "1_1") (pintype "passive"))
      (node (ref "SB5") (pin "1") (pinfunction "1_1") (pintype "passive"))
      (node (ref "U1") (pin "14") (pinfunction "ANGD_14") (pintype "passive"))
    )
    (net (code "21") (name "Net-(C17-Pad2)") (class "Default")
      (node (ref "C17") (pin "2") (pinfunction "2_2") (pintype "passive"))
      (node (ref "Q2") (pin "D") (pinfunction "D_D") (pintype "passive"))
      (node (ref "R1") (pin "2") (pinfunction "2_2") (pintype "passive"))
      (node (ref "R3") (pin "2") (pinfunction "2_2") (pintype "passive"))
      (node (ref "SB2") (pin "2") (pinfunction "2_2") (pintype "passive"))
    )
    (net (code "22") (name "Net-(C25-Pad2)") (class "Default")
      (node (ref "C25") (pin "2") (pinfunction "2_2") (pintype "passive"))
      (node (ref "R3") (pin "1") (pinfunction "1_1") (pintype "passive"))
    )
    (net (code "23") (name "Net-(C26-Pad2)") (class "Default")
      (node (ref "C26") (pin "2") (pinfunction "2_2") (pintype "passive"))
      (node (ref "R4") (pin "1") (pinfunction "1_1") (pintype "passive"))
    )
    (net (code "24") (name "Net-(C27-Pad2)") (class "Default")
      (node (ref "C27") (pin "2") (pinfunction "2_2") (pintype "passive"))
      (node (ref "R5") (pin "1") (pinfunction "1_1") (pintype "passive"))
    )
    (net (code "25") (name "Net-(C28-Pad2)") (class "Default")
      (node (ref "C28") (pin "2") (pinfunction "2_2") (pintype "passive"))
      (node (ref "R6") (pin "1") (pinfunction "1_1") (pintype "passive"))
    )
    (net (code "26") (name "Net-(C36-Pad2)") (class "Default")
      (node (ref "C36") (pin "2") (pinfunction "2_2") (pintype "passive"))
      (node (ref "R22") (pin "2") (pinfunction "2_2") (pintype "passive"))
    )
    (net (code "27") (name "Net-(C38-Pad2)") (class "Default")
      (node (ref "C38") (pin "2") (pinfunction "2_2") (pintype "passive"))
      (node (ref "R26") (pin "1") (pinfunction "1_1") (pintype "passive"))
    )
    (net (code "28") (name "Net-(C41-Pad1)") (class "Default")
      (node (ref "C41") (pin "1") (pinfunction "1_1") (pintype "passive"))
      (node (ref "R32") (pin "1") (pinfunction "1_1") (pintype "passive"))
      (node (ref "R33") (pin "1") (pinfunction "1_1") (pintype "passive"))
    )
    (net (code "29") (name "Net-(D1-A)") (class "Default")
      (node (ref "C26") (pin "1") (pinfunction "1_1") (pintype "passive"))
      (node (ref "C33") (pin "1") (pinfunction "1_1") (pintype "passive"))
      (node (ref "D1") (pin "1") (pinfunction "A_1") (pintype "passive"))
      (node (ref "L1") (pin "2") (pinfunction "2_2") (pintype "passive"))
      (node (ref "Q1") (pin "S") (pinfunction "S_S") (pintype "passive"))
      (node (ref "Q3") (pin "D") (pinfunction "D_D") (pintype "passive"))
      (node (ref "R6") (pin "2") (pinfunction "2_2") (pintype "passive"))
      (node (ref "TP6") (pin "1") (pinfunction "1_1") (pintype "passive"))
      (node (ref "U1") (pin "22") (pinfunction "SW2_22") (pintype "passive"))
    )
    (net (code "30") (name "Net-(D1-C)") (class "Default")
      (node (ref "C18") (pin "2") (pinfunction "2_2") (pintype "passive"))
      (node (ref "D1") (pin "2") (pinfunction "C_2") (pintype "passive"))
      (node (ref "Q1") (pin "D") (pinfunction "D_D") (pintype "passive"))
      (node (ref "R2") (pin "1") (pinfunction "1_1") (pintype "passive"))
      (node (ref "R4") (pin "2") (pinfunction "2_2") (pintype "passive"))
      (node (ref "SB3") (pin "2") (pinfunction "2_2") (pintype "passive"))
    )
    (net (code "31") (name "Net-(D2-C)") (class "Default")
      (node (ref "C25") (pin "1") (pinfunction "1_1") (pintype "passive"))
      (node (ref "C30") (pin "2") (pinfunction "2_2") (pintype "passive"))
      (node (ref "D2") (pin "2") (pinfunction "C_2") (pintype "passive"))
      (node (ref "L1") (pin "1") (pintype "passive"))
      (node (ref "Q2") (pin "S") (pinfunction "S_S") (pintype "passive"))
      (node (ref "Q4") (pin "D") (pinfunction "D_D") (pintype "passive"))
      (node (ref "R5") (pin "2") (pinfunction "2_2") (pintype "passive"))
      (node (ref "TP5") (pin "1") (pinfunction "1_1") (pintype "passive"))
      (node (ref "U1") (pin "27") (pinfunction "SW1_27") (pintype "passive"))
    )
    (net (code "32") (name "Net-(D3-A)") (class "Default")
      (node (ref "D3") (pin "1") (pinfunction "A_1") (pintype "passive"))
      (node (ref "Q2") (pin "G") (pinfunction "G_G") (pintype "passive"))
      (node (ref "R10") (pin "2") (pinfunction "2_2") (pintype "passive"))
    )
    (net (code "33") (name "Net-(D3-C)") (class "Default")
      (node (ref "D3") (pin "2") (pinfunction "C_2") (pintype "passive"))
      (node (ref "R10") (pin "1") (pinfunction "1_1") (pintype "passive"))
      (node (ref "R9") (pin "2") (pinfunction "2_2") (pintype "passive"))
    )
    (net (code "34") (name "Net-(D4-A)") (class "Default")
      (node (ref "D4") (pin "1") (pinfunction "A_1") (pintype "passive"))
      (node (ref "Q3") (pin "G") (pinfunction "G_G") (pintype "passive"))
      (node (ref "R13") (pin "2") (pinfunction "2_2") (pintype "passive"))
    )
    (net (code "35") (name "Net-(D4-C)") (class "Default")
      (node (ref "D4") (pin "2") (pinfunction "C_2") (pintype "passive"))
      (node (ref "R13") (pin "1") (pinfunction "1_1") (pintype "passive"))
      (node (ref "R14") (pin "2") (pinfunction "2_2") (pintype "passive"))
    )
    (net (code "36") (name "Net-(D5-A)") (class "Default")
      (node (ref "D5") (pin "1") (pinfunction "A_1") (pintype "passive"))
      (node (ref "Q4") (pin "G") (pinfunction "G_G") (pintype "passive"))
      (node (ref "R12") (pin "2") (pinfunction "2_2") (pintype "passive"))
    )
    (net (code "37") (name "Net-(D5-C)") (class "Default")
      (node (ref "D5") (pin "2") (pinfunction "C_2") (pintype "passive"))
      (node (ref "R11") (pin "2") (pinfunction "2_2") (pintype "passive"))
      (node (ref "R12") (pin "1") (pinfunction "1_1") (pintype "passive"))
    )
    (net (code "38") (name "Net-(D6-C)") (class "Default")
      (node (ref "C30") (pin "1") (pinfunction "1_1") (pintype "passive"))
      (node (ref "D6") (pin "2") (pinfunction "C_2") (pintype "passive"))
      (node (ref "U1") (pin "29") (pinfunction "BT1_29") (pintype "passive"))
    )
    (net (code "39") (name "Net-(D7-A)") (class "Default")
      (node (ref "D7") (pin "1") (pinfunction "A_1") (pintype "passive"))
      (node (ref "Q1") (pin "G") (pinfunction "G_G") (pintype "passive"))
      (node (ref "R16") (pin "2") (pinfunction "2_2") (pintype "passive"))
    )
    (net (code "40") (name "Net-(D7-C)") (class "Default")
      (node (ref "D7") (pin "2") (pinfunction "C_2") (pintype "passive"))
      (node (ref "R15") (pin "2") (pinfunction "2_2") (pintype "passive"))
      (node (ref "R16") (pin "1") (pinfunction "1_1") (pintype "passive"))
    )
    (net (code "41") (name "Net-(D8-C)") (class "Default")
      (node (ref "C33") (pin "2") (pinfunction "2_2") (pintype "passive"))
      (node (ref "D8") (pin "2") (pinfunction "C_2") (pintype "passive"))
      (node (ref "U1") (pin "20") (pinfunction "BT2_20") (pintype "passive"))
    )
    (net (code "42") (name "Net-(JP1-Pad2)") (class "Default")
      (node (ref "JP1") (pin "2") (pinfunction "2_2") (pintype "passive"))
      (node (ref "R22") (pin "1") (pinfunction "1_1") (pintype "passive"))
      (node (ref "R23") (pin "2") (pinfunction "2_2") (pintype "passive"))
    )
    (net (code "43") (name "Net-(P6-Pad2)") (class "Default")
      (node (ref "P6") (pin "2") (pinfunction "2_2") (pintype "passive"))
      (node (ref "R29") (pin "1") (pinfunction "1_1") (pintype "passive"))
    )
    (net (code "44") (name "Net-(P7-Pad2)") (class "Default")
      (node (ref "P7") (pin "2") (pinfunction "2_2") (pintype "passive"))
      (node (ref "R30") (pin "1") (pinfunction "1_1") (pintype "passive"))
    )
    (net (code "45") (name "Net-(Q5-D)") (class "Default")
      (node (ref "Q5") (pin "3") (pinfunction "D_3") (pintype "passive"))
      (node (ref "R28") (pin "1") (pinfunction "1_1") (pintype "passive"))
      (node (ref "R32") (pin "2") (pinfunction "2_2") (pintype "passive"))
    )
    (net (code "46") (name "Net-(Q5-G)") (class "Default")
      (node (ref "Q5") (pin "1") (pinfunction "G_1") (pintype "passive"))
      (node (ref "R31") (pin "1") (pinfunction "1_1") (pintype "passive"))
      (node (ref "R35") (pin "2") (pinfunction "2_2") (pintype "passive"))
    )
    (net (code "47") (name "Net-(R24-Pad1)") (class "Default")
      (node (ref "R24") (pin "1") (pinfunction "1_1") (pintype "passive"))
      (node (ref "TP7") (pin "1") (pinfunction "1_1") (pintype "passive"))
    )
    (net (code "48") (name "Net-(U1-COMP)") (class "Default")
      (node (ref "C37") (pin "2") (pinfunction "2_2") (pintype "passive"))
      (node (ref "R26") (pin "2") (pinfunction "2_2") (pintype "passive"))
      (node (ref "U1") (pin "15") (pinfunction "COMP_15") (pintype "passive"))
    )
    (net (code "49") (name "Net-(U1-DT)") (class "Default")
      (node (ref "R21") (pin "2") (pinfunction "2_2") (pintype "passive"))
      (node (ref "U1") (pin "8") (pinfunction "DT_8") (pintype "passive"))
    )
    (net (code "50") (name "Net-(U1-FB)") (class "Default")
      (node (ref "C36") (pin "1") (pinfunction "1_1") (pintype "passive"))
      (node (ref "R23") (pin "1") (pinfunction "1_1") (pintype "passive"))
      (node (ref "R24") (pin "2") (pinfunction "2_2") (pintype "passive"))
      (node (ref "R25") (pin "2") (pinfunction "2_2") (pintype "passive"))
      (node (ref "U1") (pin "16") (pinfunction "FB_16") (pintype "passive"))
    )
    (net (code "51") (name "Net-(U1-FREQ)") (class "Default")
      (node (ref "R27") (pin "2") (pinfunction "2_2") (pintype "passive"))
      (node (ref "U1") (pin "10") (pinfunction "FREQ_10") (pintype "passive"))
    )
    (net (code "52") (name "Net-(U1-HD1)") (class "Default")
      (node (ref "R9") (pin "1") (pinfunction "1_1") (pintype "passive"))
      (node (ref "U1") (pin "28") (pinfunction "HD1_28") (pintype "passive"))
    )
    (net (code "53") (name "Net-(U1-HD2)") (class "Default")
      (node (ref "R15") (pin "1") (pinfunction "1_1") (pintype "passive"))
      (node (ref "U1") (pin "21") (pinfunction "HD2_21") (pintype "passive"))
    )
    (net (code "54") (name "Net-(U1-LD1)") (class "Default")
      (node (ref "R11") (pin "1") (pinfunction "1_1") (pintype "passive"))
      (node (ref "U1") (pin "26") (pinfunction "LD1_26") (pintype "passive"))
    )
    (net (code "55") (name "Net-(U1-LD2)") (class "Default")
      (node (ref "R14") (pin "1") (pinfunction "1_1") (pintype "passive"))
      (node (ref "U1") (pin "23") (pinfunction "LD2_23") (pintype "passive"))
    )
    (net (code "56") (name "PGND") (class "Default")
      (node (ref "C1") (pin "2") (pinfunction "2_2") (pintype "passive"))
      (node (ref "C10") (pin "2") (pinfunction "2_2") (pintype "passive"))
      (node (ref "C11") (pin "2") (pinfunction "2_2") (pintype "passive"))
      (node (ref "C12") (pin "1") (pinfunction "1_1") (pintype "passive"))
      (node (ref "C13") (pin "1") (pinfunction "1_1") (pintype "passive"))
      (node (ref "C14") (pin "1") (pinfunction "1_1") (pintype "passive"))
      (node (ref "C15") (pin "1") (pinfunction "1_1") (pintype "passive"))
      (node (ref "C16") (pin "1") (pinfunction "1_1") (pintype "passive"))
      (node (ref "C17") (pin "1") (pinfunction "1_1") (pintype "passive"))
      (node (ref "C18") (pin "1") (pinfunction "1_1") (pintype "passive"))
      (node (ref "C19") (pin "1") (pinfunction "1_1") (pintype "passive"))
      (node (ref "C2") (pin "1") (pinfunction "1_1") (pintype "passive"))
      (node (ref "C20") (pin "1") (pinfunction "1_1") (pintype "passive"))
      (node (ref "C21") (pin "1") (pinfunction "1_1") (pintype "passive"))
      (node (ref "C22") (pin "1") (pinfunction "1_1") (pintype "passive"))
      (node (ref "C23") (pin "1") (pinfunction "1_1") (pintype "passive"))
      (node (ref "C24") (pin "2") (pinfunction "2_2") (pintype "passive"))
      (node (ref "C27") (pin "1") (pinfunction "1_1") (pintype "passive"))
      (node (ref "C28") (pin "1") (pinfunction "1_1") (pintype "passive"))
      (node (ref "C3") (pin "1") (pinfunction "1_1") (pintype "passive"))
      (node (ref "C31") (pin "2") (pinfunction "2_2") (pintype "passive"))
      (node (ref "C32") (pin "2") (pinfunction "2_2") (pintype "passive"))
      (node (ref "C34") (pin "2") (pinfunction "2_2") (pintype "passive"))
      (node (ref "C4") (pin "1") (pinfunction "1_1") (pintype "passive"))
      (node (ref "C5") (pin "1") (pinfunction "1_1") (pintype "passive"))
      (node (ref "C6") (pin "1") (pinfunction "1_1") (pintype "passive"))
      (node (ref "C7") (pin "1") (pinfunction "1_1") (pintype "passive"))
      (node (ref "C8") (pin "1") (pinfunction "1_1") (pintype "passive"))
      (node (ref "C9") (pin "1") (pinfunction "1_1") (pintype "passive"))
      (node (ref "D2") (pin "1") (pinfunction "A_1") (pintype "passive"))
      (node (ref "J3") (pin "1") (pinfunction "1_1") (pintype "passive"))
      (node (ref "J4") (pin "1") (pinfunction "1_1") (pintype "passive"))
      (node (ref "Q3") (pin "S") (pinfunction "S_S") (pintype "passive"))
      (node (ref "Q4") (pin "S") (pinfunction "S_S") (pintype "passive"))
      (node (ref "SB5") (pin "2") (pinfunction "2_2") (pintype "passive"))
      (node (ref "TP3") (pin "1") (pinfunction "1_1") (pintype "passive"))
      (node (ref "TP4") (pin "1") (pinfunction "1_1") (pintype "passive"))
      (node (ref "U1") (pin "25") (pinfunction "PGND_25") (pintype "passive"))
      (node (ref "U1") (pin "33") (pinfunction "PGND_33") (pintype "passive"))
    )
    (net (code "57") (name "unconnected-(H1-Pad1)") (class "Default")
      (node (ref "H1") (pin "1") (pinfunction "1_1") (pintype "passive+no_connect"))
    )
    (net (code "58") (name "unconnected-(H2-Pad1)") (class "Default")
      (node (ref "H2") (pin "1") (pinfunction "1_1") (pintype "passive+no_connect"))
    )
    (net (code "59") (name "unconnected-(H3-Pad1)") (class "Default")
      (node (ref "H3") (pin "1") (pinfunction "1_1") (pintype "passive+no_connect"))
    )
    (net (code "60") (name "unconnected-(H4-Pad1)") (class "Default")
      (node (ref "H4") (pin "1") (pinfunction "1_1") (pintype "passive+no_connect"))
    )
    (net (code "61") (name "unconnected-(U1-NC-Pad2)") (class "Default")
      (node (ref "U1") (pin "2") (pinfunction "NC_2") (pintype "passive+no_connect"))
    )
    (net (code "62") (name "unconnected-(U1-NC-Pad7)") (class "Default")
      (node (ref "U1") (pin "7") (pinfunction "NC_7") (pintype "passive+no_connect"))
    )
    (net (code "63") (name "unconnected-(U1-NC-Pad9)") (class "Default")
      (node (ref "U1") (pin "9") (pinfunction "NC_9") (pintype "passive+no_connect"))
    )
    (net (code "64") (name "unconnected-(U1-NC-Pad13)") (class "Default")
      (node (ref "U1") (pin "13") (pinfunction "NC_13") (pintype "passive+no_connect"))
    )
  )
)
